# 5_POWER.net
KiCad netlist of a schematic drawn in Altium Designer
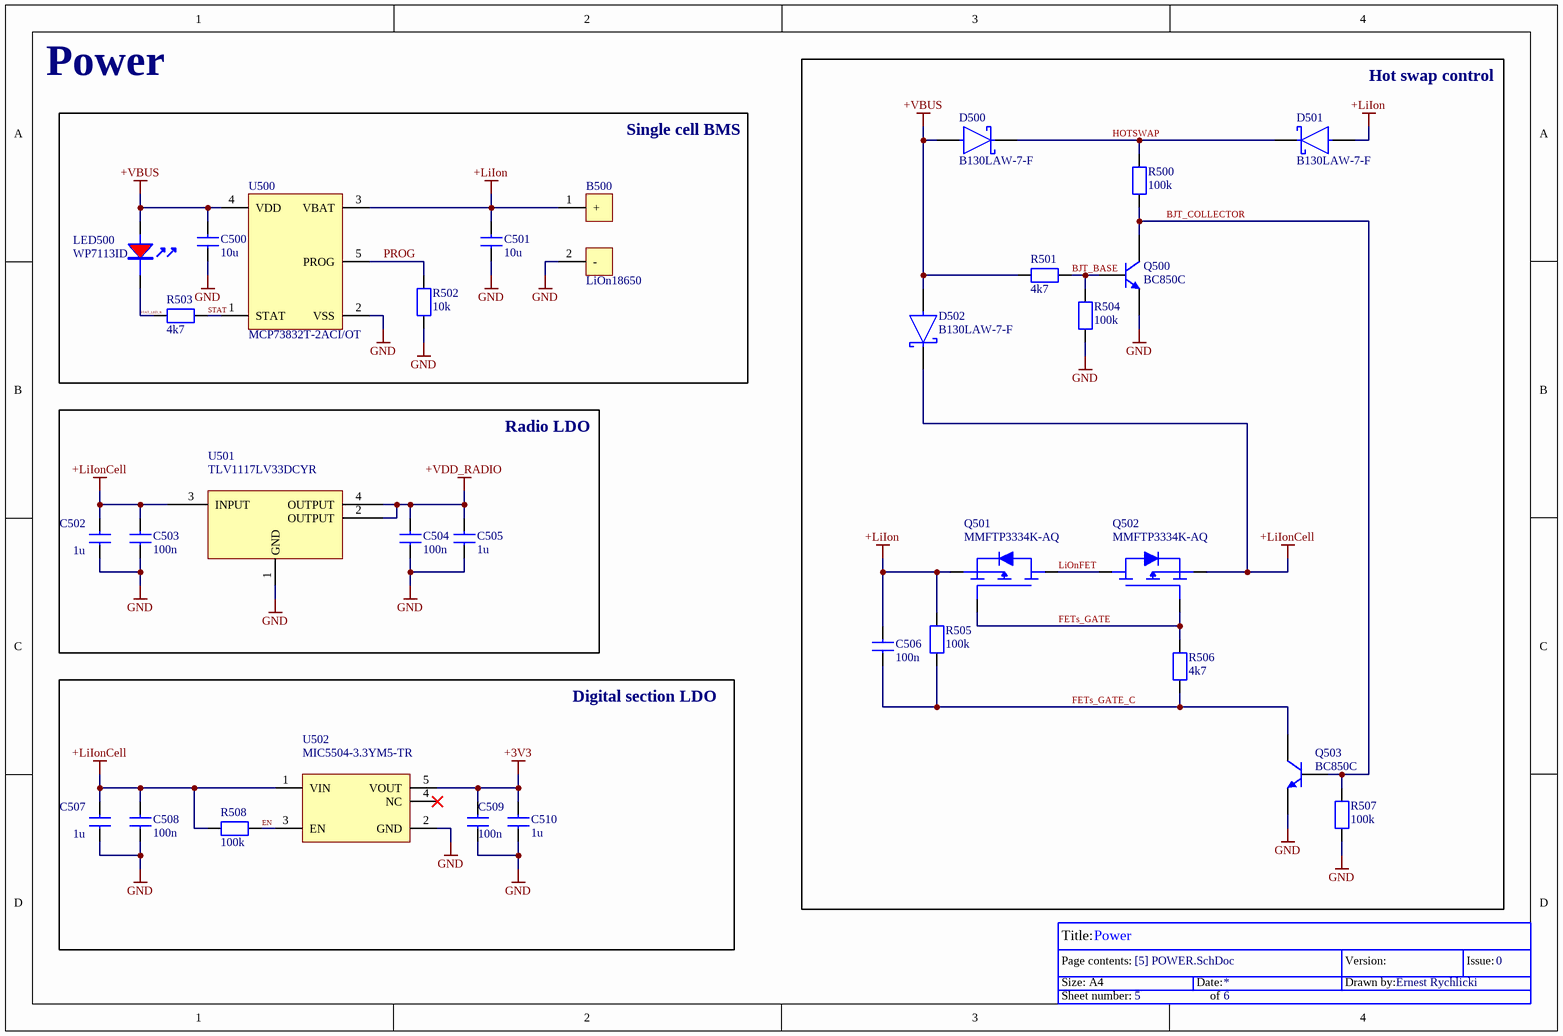
[diagram p0: [5] POWER.SchDoc]

(export (version "E")
  (design (tool "Eeschema 10.0.6"))
  (components
    (comp (ref "B500")
      (value "LiOn18650")
      (footprint "LION18650")
      (description "LiOn18650 - single cell battery, soldered to PCB")
      (libsource (lib "ER_SCH_LIB") (part "LiOn18650"))
    )
    (comp (ref "C500")
      (value "10u")
      (footprint "C0402")
      (description "Capacitor Ceramic Mlcc 0402 10UF 6.3V SMD")
      (fields
        (field (name "MANUFACTURER") "Murata")
        (field (name "MANUFACTURER PART NUMBER") "GRJ155R60J106ME11D")
      )
      (libsource (lib "ER_SCH_LIB") (part "GRJ155R60J106ME11D"))
    )
    (comp (ref "C501")
      (value "10u")
      (footprint "C0402")
      (description "Capacitor Ceramic Mlcc 0402 10UF 6.3V SMD")
      (fields
        (field (name "MANUFACTURER") "Murata")
        (field (name "MANUFACTURER PART NUMBER") "GRJ155R60J106ME11D")
      )
      (libsource (lib "ER_SCH_LIB") (part "GRJ155R60J106ME11D"))
    )
    (comp (ref "C502")
      (value "1u")
      (footprint "C0402")
      (description "Multilayer Ceramic Capacitor, 1 uF, 10%, X5r, 10 V, 0402 [1005 Metric]")
      (fields
        (field (name "MANUFACTURER") "Walsin Technologies")
        (field (name "MANUFACTURER PART NUMBER") "0402X105K100CT")
      )
      (libsource (lib "ER_SCH_LIB") (part "0402X105K100CT"))
    )
    (comp (ref "C503")
      (value "100n")
      (footprint "C0402")
      (description "Multilayer Ceramic Capacitor, 0.1 uF, 25 V, ± 10%, X7R, 0402 [1005 Metric]")
      (fields
        (field (name "MANUFACTURER") "Kyocera AVX")
        (field (name "MANUFACTURER PART NUMBER") "04023C104KAT2A")
      )
      (libsource (lib "ER_SCH_LIB") (part "04023C104KAT2A"))
    )
    (comp (ref "C504")
      (value "100n")
      (footprint "C0402")
      (description "Multilayer Ceramic Capacitor, 0.1 uF, 25 V, ± 10%, X7R, 0402 [1005 Metric]")
      (fields
        (field (name "MANUFACTURER") "Kyocera AVX")
        (field (name "MANUFACTURER PART NUMBER") "04023C104KAT2A")
      )
      (libsource (lib "ER_SCH_LIB") (part "04023C104KAT2A"))
    )
    (comp (ref "C505")
      (value "1u")
      (footprint "C0402")
      (description "Multilayer Ceramic Capacitor, 1 uF, 10%, X5r, 10 V, 0402 [1005 Metric]")
      (fields
        (field (name "MANUFACTURER") "Walsin Technologies")
        (field (name "MANUFACTURER PART NUMBER") "0402X105K100CT")
      )
      (libsource (lib "ER_SCH_LIB") (part "0402X105K100CT"))
    )
    (comp (ref "C506")
      (value "100n")
      (footprint "C0402")
      (description "Multilayer Ceramic Capacitor, 0.1 uF, 25 V, ± 10%, X7R, 0402 [1005 Metric]")
      (fields
        (field (name "MANUFACTURER") "Kyocera AVX")
        (field (name "MANUFACTURER PART NUMBER") "04023C104KAT2A")
      )
      (libsource (lib "ER_SCH_LIB") (part "04023C104KAT2A"))
    )
    (comp (ref "C507")
      (value "1u")
      (footprint "C0402")
      (description "Multilayer Ceramic Capacitor, 1 uF, 10%, X5r, 10 V, 0402 [1005 Metric]")
      (fields
        (field (name "MANUFACTURER") "Walsin Technologies")
        (field (name "MANUFACTURER PART NUMBER") "0402X105K100CT")
      )
      (libsource (lib "ER_SCH_LIB") (part "0402X105K100CT"))
    )
    (comp (ref "C508")
      (value "100n")
      (footprint "C0402")
      (description "Multilayer Ceramic Capacitor, 0.1 uF, 25 V, ± 10%, X7R, 0402 [1005 Metric]")
      (fields
        (field (name "MANUFACTURER") "Kyocera AVX")
        (field (name "MANUFACTURER PART NUMBER") "04023C104KAT2A")
      )
      (libsource (lib "ER_SCH_LIB") (part "04023C104KAT2A"))
    )
    (comp (ref "C509")
      (value "100n")
      (footprint "C0402")
      (description "Multilayer Ceramic Capacitor, 0.1 uF, 25 V, ± 10%, X7R, 0402 [1005 Metric]")
      (fields
        (field (name "MANUFACTURER") "Kyocera AVX")
        (field (name "MANUFACTURER PART NUMBER") "04023C104KAT2A")
      )
      (libsource (lib "ER_SCH_LIB") (part "04023C104KAT2A"))
    )
    (comp (ref "C510")
      (value "1u")
      (footprint "C0402")
      (description "Multilayer Ceramic Capacitor, 1 uF, 10%, X5r, 10 V, 0402 [1005 Metric]")
      (fields
        (field (name "MANUFACTURER") "Walsin Technologies")
        (field (name "MANUFACTURER PART NUMBER") "0402X105K100CT")
      )
      (libsource (lib "ER_SCH_LIB") (part "0402X105K100CT"))
    )
    (comp (ref "D500")
      (value "B130LAW-7-F")
      (footprint "SOD-123")
      (description "Rectifier Diode Schottky 30V 1A 2-Pin SOD-123 T/R / DIODE SCHOTTKY 30V 1A SOD123")
      (fields (field (name "MANUFACTURER") "Diodes"))
      (libsource (lib "ER_SCH_LIB") (part "B130LAW-7-F"))
    )
    (comp (ref "D501")
      (value "B130LAW-7-F")
      (footprint "SOD-123")
      (description "Rectifier Diode Schottky 30V 1A 2-Pin SOD-123 T/R / DIODE SCHOTTKY 30V 1A SOD123")
      (fields (field (name "MANUFACTURER") "Diodes"))
      (libsource (lib "ER_SCH_LIB") (part "B130LAW-7-F"))
    )
    (comp (ref "D502")
      (value "B130LAW-7-F")
      (footprint "SOD-123")
      (description "Rectifier Diode Schottky 30V 1A 2-Pin SOD-123 T/R / DIODE SCHOTTKY 30V 1A SOD123")
      (fields (field (name "MANUFACTURER") "Diodes"))
      (libsource (lib "ER_SCH_LIB") (part "B130LAW-7-F"))
    )
    (comp (ref "LED500")
      (value "WP7113ID")
      (footprint "LED5mm")
      (description "Red T-1 3/4 5 mm 30° 50 mcd 2.2 V Tinted Solid State LED Lamp Through Hole")
      (fields (field (name "MANUFACTURER") "Kingbright"))
      (libsource (lib "ER_SCH_LIB") (part "WP7113ID"))
    )
    (comp (ref "Q500")
      (value "BC850C")
      (footprint "SOT23")
      (description "Trans GP BJT NPN 45V 0.1A 250mW Automotive 3-Pin SOT-23 T/R")
      (fields (field (name "MANUFACTURER") "Diotec"))
      (libsource (lib "ER_SCH_LIB") (part "BC850C"))
    )
    (comp (ref "Q501")
      (value "MMFTP3334K-AQ")
      (footprint "SOT23")
      (description "Mosfet, SOT-23, 30V, 4A, P, 1W")
      (fields (field (name "MANUFACTURER") "Diotec"))
      (libsource (lib "ER_SCH_LIB") (part "MMFTP3334K-AQ"))
    )
    (comp (ref "Q502")
      (value "MMFTP3334K-AQ")
      (footprint "SOT23")
      (description "Mosfet, SOT-23, 30V, 4A, P, 1W")
      (fields (field (name "MANUFACTURER") "Diotec"))
      (libsource (lib "ER_SCH_LIB") (part "MMFTP3334K-AQ"))
    )
    (comp (ref "Q503")
      (value "BC850C")
      (footprint "SOT23")
      (description "Trans GP BJT NPN 45V 0.1A 250mW Automotive 3-Pin SOT-23 T/R")
      (fields (field (name "MANUFACTURER") "Diotec"))
      (libsource (lib "ER_SCH_LIB") (part "BC850C"))
    )
    (comp (ref "R500")
      (value "100k")
      (footprint "R0603")
      (description "CRCW Thick Film Commodity Chip Resistor 0603 Size 100K Ohm 1% 0.1 W 100 ppm/K 2-Pin SMD Paper T/R")
      (fields
        (field (name "MANUFACTURER") "Vishay")
        (field (name "MANUFACTURER PART NUMBER") "CRCW0603100KFKEBC")
      )
      (libsource (lib "ER_SCH_LIB") (part "CRCW0603100KFKEBC"))
    )
    (comp (ref "R501")
      (value "4k7")
      (footprint "R0603")
      (description "Res Thick Film 0603 4.7K Ohm 1% 1/10W ±100ppm/°C Molded SMD Paper T/R")
      (fields
        (field (name "MANUFACTURER") "Yageo")
        (field (name "MANUFACTURER PART NUMBER") "AF0603FR-074K7L")
      )
      (libsource (lib "ER_SCH_LIB") (part "AF0603FR-074K7L"))
    )
    (comp (ref "R502")
      (value "10k")
      (footprint "R0603")
      (description "SMD Chip Resistor, 10 kOhm, ± 5%, 100 mW, 0603 [1608 Metric], Thick Film, General Purpose")
      (fields
        (field (name "MANUFACTURER") "Yageo")
        (field (name "MANUFACTURER PART NUMBER") "AC0603JR-0710KL")
      )
      (libsource (lib "ER_SCH_LIB") (part "AC0603JR-0710KL"))
    )
    (comp (ref "R503")
      (value "4k7")
      (footprint "R0603")
      (description "Res Thick Film 0603 4.7K Ohm 1% 1/10W ±100ppm/°C Molded SMD Paper T/R")
      (fields
        (field (name "MANUFACTURER") "Yageo")
        (field (name "MANUFACTURER PART NUMBER") "AF0603FR-074K7L")
      )
      (libsource (lib "ER_SCH_LIB") (part "AF0603FR-074K7L"))
    )
    (comp (ref "R504")
      (value "100k")
      (footprint "R0603")
      (description "CRCW Thick Film Commodity Chip Resistor 0603 Size 100K Ohm 1% 0.1 W 100 ppm/K 2-Pin SMD Paper T/R")
      (fields
        (field (name "MANUFACTURER") "Vishay")
        (field (name "MANUFACTURER PART NUMBER") "CRCW0603100KFKEBC")
      )
      (libsource (lib "ER_SCH_LIB") (part "CRCW0603100KFKEBC"))
    )
    (comp (ref "R505")
      (value "100k")
      (footprint "R0603")
      (description "CRCW Thick Film Commodity Chip Resistor 0603 Size 100K Ohm 1% 0.1 W 100 ppm/K 2-Pin SMD Paper T/R")
      (fields
        (field (name "MANUFACTURER") "Vishay")
        (field (name "MANUFACTURER PART NUMBER") "CRCW0603100KFKEBC")
      )
      (libsource (lib "ER_SCH_LIB") (part "CRCW0603100KFKEBC"))
    )
    (comp (ref "R506")
      (value "4k7")
      (footprint "R0603")
      (description "Res Thick Film 0603 4.7K Ohm 1% 1/10W ±100ppm/°C Molded SMD Paper T/R")
      (fields
        (field (name "MANUFACTURER") "Yageo")
        (field (name "MANUFACTURER PART NUMBER") "AF0603FR-074K7L")
      )
      (libsource (lib "ER_SCH_LIB") (part "AF0603FR-074K7L"))
    )
    (comp (ref "R507")
      (value "100k")
      (footprint "R0603")
      (description "CRCW Thick Film Commodity Chip Resistor 0603 Size 100K Ohm 1% 0.1 W 100 ppm/K 2-Pin SMD Paper T/R")
      (fields
        (field (name "MANUFACTURER") "Vishay")
        (field (name "MANUFACTURER PART NUMBER") "CRCW0603100KFKEBC")
      )
      (libsource (lib "ER_SCH_LIB") (part "CRCW0603100KFKEBC"))
    )
    (comp (ref "R508")
      (value "100k")
      (footprint "R0603")
      (description "CRCW Thick Film Commodity Chip Resistor 0603 Size 100K Ohm 1% 0.1 W 100 ppm/K 2-Pin SMD Paper T/R")
      (fields
        (field (name "MANUFACTURER") "Vishay")
        (field (name "MANUFACTURER PART NUMBER") "CRCW0603100KFKEBC")
      )
      (libsource (lib "ER_SCH_LIB") (part "CRCW0603100KFKEBC"))
    )
    (comp (ref "U500")
      (value "MCP73832T-2ACI/OT")
      (footprint "SOT23-5")
      (description "MCP73832 Series Single-Cell Li-Ion/Li-Polymer Battery Charge Controller SOT-23-5")
      (fields (field (name "MANUFACTURER") "Microchip"))
      (libsource (lib "ER_SCH_LIB") (part "MCP73832T-2ACI/OT"))
    )
    (comp (ref "U501")
      (value "TLV1117LV33DCYR")
      (footprint "SOT223-4")
      (description "IC REG LDO 3.3V 1A SOT223")
      (fields (field (name "MANUFACTURER") "Texas Instruments"))
      (libsource (lib "ER_SCH_LIB") (part "TLV1117LV33DCYR"))
    )
    (comp (ref "U502")
      (value "MIC5504-3.3YM5-TR")
      (footprint "SOT23-5")
      (description "LDO Regulator Pos 3.3V 0.3A Medical 5-Pin SOT-23 T/R / IC REG LDO 3.3V 0.3A SOT-23-5")
      (fields (field (name "MANUFACTURER") "Microchip"))
      (libsource (lib "ER_SCH_LIB") (part "MIC5504-3.3YM5-TR"))
    )
  )
  (nets
    (net (code "1") (name "+3V3") (class "Default")
      (node (ref "C509") (pin "2") (pinfunction "2_2") (pintype "passive"))
      (node (ref "C510") (pin "2") (pinfunction "2_2") (pintype "passive"))
      (node (ref "U502") (pin "5") (pinfunction "VOUT_5") (pintype "passive"))
    )
    (net (code "2") (name "+LiIon") (class "Default")
      (node (ref "B500") (pin "1") (pinfunction "+_1") (pintype "power_in"))
      (node (ref "C501") (pin "2") (pinfunction "2_2") (pintype "passive"))
      (node (ref "C506") (pin "2") (pinfunction "2_2") (pintype "passive"))
      (node (ref "D501") (pin "2") (pinfunction "A_2") (pintype "passive"))
      (node (ref "Q501") (pin "2") (pinfunction "S_2") (pintype "power_in"))
      (node (ref "R505") (pin "2") (pinfunction "2_2") (pintype "passive"))
      (node (ref "U500") (pin "3") (pinfunction "VBAT_3") (pintype "power_in"))
    )
    (net (code "3") (name "+LiIonCell") (class "Default")
      (node (ref "C502") (pin "2") (pinfunction "2_2") (pintype "passive"))
      (node (ref "C503") (pin "2") (pinfunction "2_2") (pintype "passive"))
      (node (ref "C507") (pin "2") (pinfunction "2_2") (pintype "passive"))
      (node (ref "C508") (pin "2") (pinfunction "2_2") (pintype "passive"))
      (node (ref "D502") (pin "1") (pinfunction "C_1") (pintype "passive"))
      (node (ref "Q502") (pin "2") (pinfunction "S_2") (pintype "power_in"))
      (node (ref "R508") (pin "2") (pinfunction "2_2") (pintype "passive"))
      (node (ref "U501") (pin "3") (pinfunction "INPUT_3") (pintype "passive"))
      (node (ref "U502") (pin "1") (pinfunction "VIN_1") (pintype "passive"))
    )
    (net (code "4") (name "+VBUS") (class "Default")
      (node (ref "C500") (pin "2") (pinfunction "2_2") (pintype "passive"))
      (node (ref "D500") (pin "2") (pinfunction "A_2") (pintype "passive"))
      (node (ref "D502") (pin "2") (pinfunction "A_2") (pintype "passive"))
      (node (ref "LED500") (pin "A") (pinfunction "A_A") (pintype "passive"))
      (node (ref "R501") (pin "2") (pinfunction "2_2") (pintype "passive"))
      (node (ref "U500") (pin "4") (pinfunction "VDD_4") (pintype "power_in"))
    )
    (net (code "5") (name "+VDD_RADIO") (class "Default")
      (node (ref "C504") (pin "2") (pinfunction "2_2") (pintype "passive"))
      (node (ref "C505") (pin "2") (pinfunction "2_2") (pintype "passive"))
      (node (ref "U501") (pin "2") (pinfunction "OUTPUT_2") (pintype "passive"))
      (node (ref "U501") (pin "4") (pinfunction "OUTPUT_4") (pintype "passive"))
    )
    (net (code "6") (name "/BJT_BASE") (class "Default")
      (node (ref "Q500") (pin "1") (pinfunction "B_1") (pintype "passive"))
      (node (ref "R501") (pin "1") (pinfunction "1_1") (pintype "passive"))
      (node (ref "R504") (pin "2") (pinfunction "2_2") (pintype "passive"))
    )
    (net (code "7") (name "/BJT_COLLECTOR") (class "Default")
      (node (ref "Q500") (pin "3") (pinfunction "C_3") (pintype "passive"))
      (node (ref "Q503") (pin "1") (pinfunction "B_1") (pintype "passive"))
      (node (ref "R500") (pin "1") (pinfunction "1_1") (pintype "passive"))
      (node (ref "R507") (pin "2") (pinfunction "2_2") (pintype "passive"))
    )
    (net (code "8") (name "/EN") (class "Default")
      (node (ref "R508") (pin "1") (pinfunction "1_1") (pintype "passive"))
      (node (ref "U502") (pin "3") (pinfunction "EN_3") (pintype "passive"))
    )
    (net (code "9") (name "/FETs_GATE") (class "Default")
      (node (ref "Q501") (pin "1") (pinfunction "G_1") (pintype "power_in"))
      (node (ref "Q502") (pin "1") (pinfunction "G_1") (pintype "power_in"))
      (node (ref "R506") (pin "1") (pinfunction "1_1") (pintype "passive"))
    )
    (net (code "10") (name "/FETs_GATE_C") (class "Default")
      (node (ref "C506") (pin "1") (pinfunction "1_1") (pintype "passive"))
      (node (ref "Q503") (pin "3") (pinfunction "C_3") (pintype "passive"))
      (node (ref "R505") (pin "1") (pinfunction "1_1") (pintype "passive"))
      (node (ref "R506") (pin "2") (pinfunction "2_2") (pintype "passive"))
    )
    (net (code "11") (name "/HOTSWAP") (class "Default")
      (node (ref "D500") (pin "1") (pinfunction "C_1") (pintype "passive"))
      (node (ref "D501") (pin "1") (pinfunction "C_1") (pintype "passive"))
      (node (ref "R500") (pin "2") (pinfunction "2_2") (pintype "passive"))
    )
    (net (code "12") (name "/LiOnFET") (class "Default")
      (node (ref "Q501") (pin "3") (pinfunction "D_3") (pintype "power_in"))
      (node (ref "Q502") (pin "3") (pinfunction "D_3") (pintype "power_in"))
    )
    (net (code "13") (name "/PROG") (class "Default")
      (node (ref "R502") (pin "2") (pinfunction "2_2") (pintype "passive"))
      (node (ref "U500") (pin "5") (pinfunction "PROG_5") (pintype "power_in"))
    )
    (net (code "14") (name "/STAT") (class "Default")
      (node (ref "R503") (pin "1") (pinfunction "1_1") (pintype "passive"))
      (node (ref "U500") (pin "1") (pinfunction "STAT_1") (pintype "power_in"))
    )
    (net (code "15") (name "/STAT_LED_K") (class "Default")
      (node (ref "LED500") (pin "K") (pinfunction "K_K") (pintype "passive"))
      (node (ref "R503") (pin "2") (pinfunction "2_2") (pintype "passive"))
    )
    (net (code "16") (name "GND") (class "Default")
      (node (ref "B500") (pin "2") (pinfunction "-_2") (pintype "power_in"))
      (node (ref "C500") (pin "1") (pinfunction "1_1") (pintype "passive"))
      (node (ref "C501") (pin "1") (pinfunction "1_1") (pintype "passive"))
      (node (ref "C502") (pin "1") (pinfunction "1_1") (pintype "passive"))
      (node (ref "C503") (pin "1") (pinfunction "1_1") (pintype "passive"))
      (node (ref "C504") (pin "1") (pinfunction "1_1") (pintype "passive"))
      (node (ref "C505") (pin "1") (pinfunction "1_1") (pintype "passive"))
      (node (ref "C507") (pin "1") (pinfunction "1_1") (pintype "passive"))
      (node (ref "C508") (pin "1") (pinfunction "1_1") (pintype "passive"))
      (node (ref "C509") (pin "1") (pinfunction "1_1") (pintype "passive"))
      (node (ref "C510") (pin "1") (pinfunction "1_1") (pintype "passive"))
      (node (ref "Q500") (pin "2") (pinfunction "E_2") (pintype "passive"))
      (node (ref "Q503") (pin "2") (pinfunction "E_2") (pintype "passive"))
      (node (ref "R502") (pin "1") (pinfunction "1_1") (pintype "passive"))
      (node (ref "R504") (pin "1") (pinfunction "1_1") (pintype "passive"))
      (node (ref "R507") (pin "1") (pinfunction "1_1") (pintype "passive"))
      (node (ref "U500") (pin "2") (pinfunction "VSS_2") (pintype "power_in"))
      (node (ref "U501") (pin "1") (pinfunction "GND_1") (pintype "passive"))
      (node (ref "U502") (pin "2") (pinfunction "GND_2") (pintype "passive"))
    )
    (net (code "17") (name "unconnected-(U502-NC-Pad4)") (class "Default")
      (node (ref "U502") (pin "4") (pinfunction "NC_4") (pintype "passive+no_connect"))
    )
  )
)
